# FSRs.net
KiCad netlist of a schematic drawn in Altium Designer
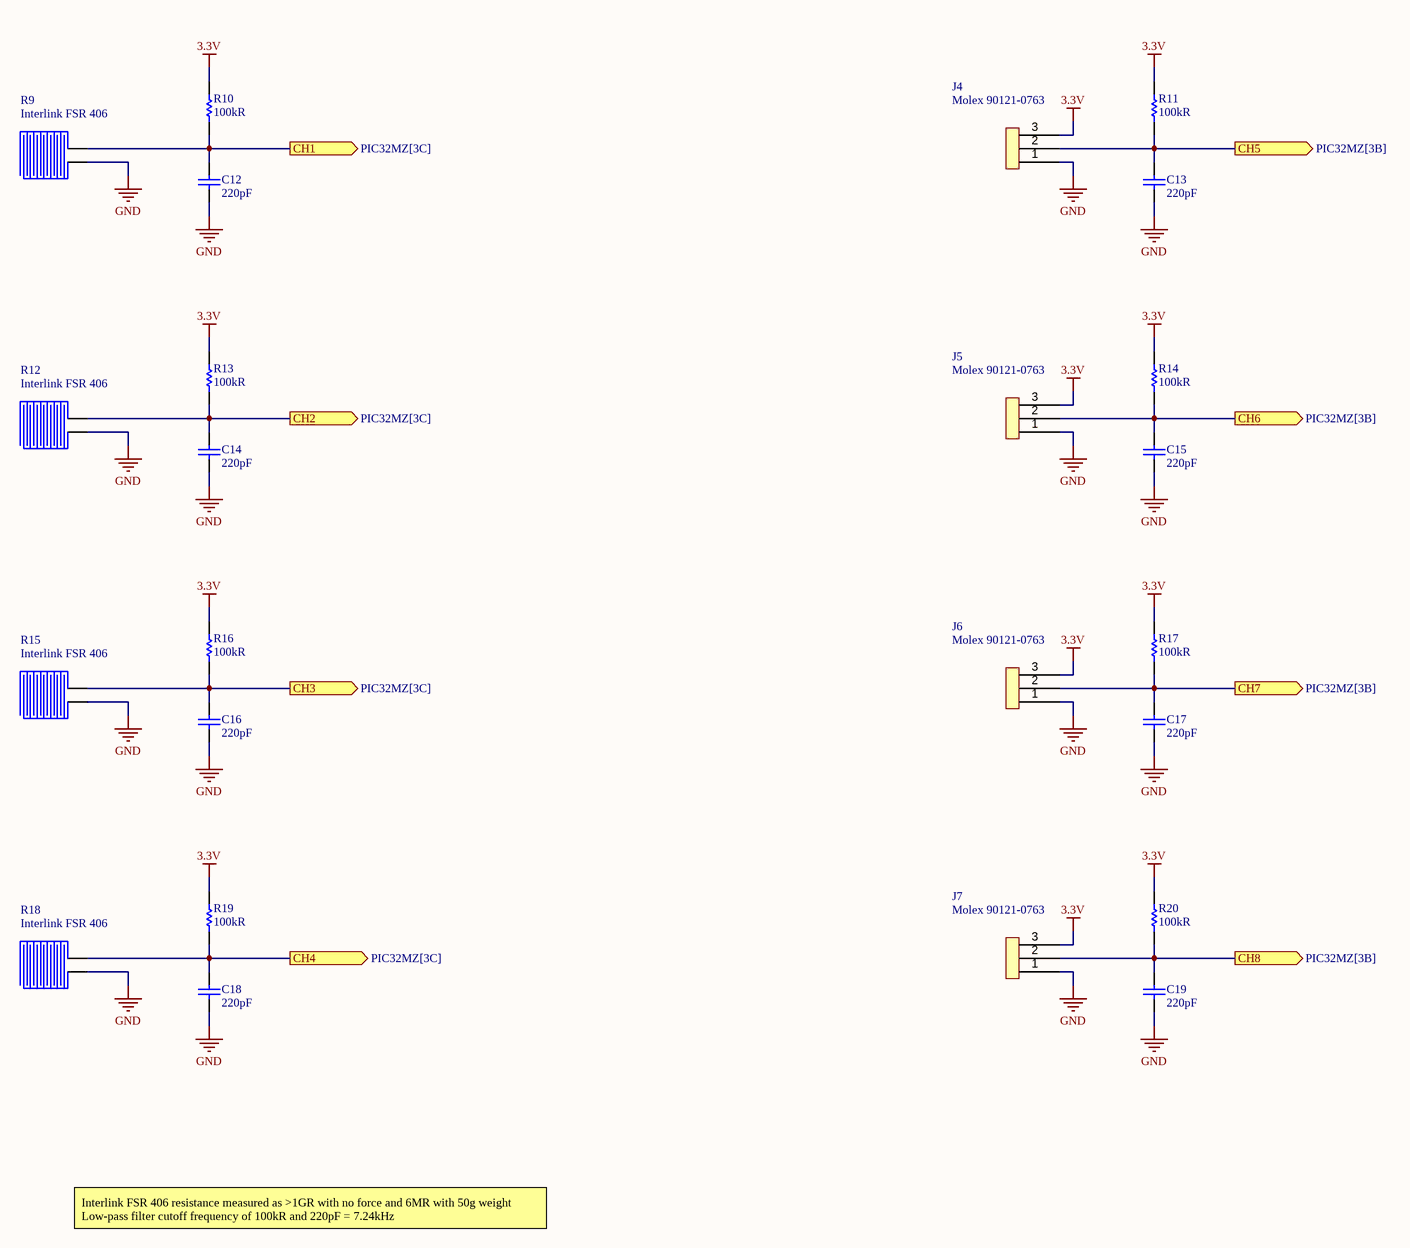
[diagram p0: FSRs.SchDoc]

(export (version "E")
  (design (tool "Eeschema 10.0.6"))
  (components
    (comp (ref "C12")
      (value "220pF")
      (footprint "Capacitor 0402")
      (libsource (lib "x-io") (part "Capacitor"))
    )
    (comp (ref "C13")
      (value "220pF")
      (footprint "Capacitor 0402")
      (libsource (lib "x-io") (part "Capacitor"))
    )
    (comp (ref "C14")
      (value "220pF")
      (footprint "Capacitor 0402")
      (libsource (lib "x-io") (part "Capacitor"))
    )
    (comp (ref "C15")
      (value "220pF")
      (footprint "Capacitor 0402")
      (libsource (lib "x-io") (part "Capacitor"))
    )
    (comp (ref "C16")
      (value "220pF")
      (footprint "Capacitor 0402")
      (libsource (lib "x-io") (part "Capacitor"))
    )
    (comp (ref "C17")
      (value "220pF")
      (footprint "Capacitor 0402")
      (libsource (lib "x-io") (part "Capacitor"))
    )
    (comp (ref "C18")
      (value "220pF")
      (footprint "Capacitor 0402")
      (libsource (lib "x-io") (part "Capacitor"))
    )
    (comp (ref "C19")
      (value "220pF")
      (footprint "Capacitor 0402")
      (libsource (lib "x-io") (part "Capacitor"))
    )
    (comp (ref "J4")
      (value "Molex 90121-0763")
      (footprint "Molex 90121-0763")
      (libsource (lib "x-io") (part "Molex 90121-0763"))
    )
    (comp (ref "J5")
      (value "Molex 90121-0763")
      (footprint "Molex 90121-0763")
      (libsource (lib "x-io") (part "Molex 90121-0763"))
    )
    (comp (ref "J6")
      (value "Molex 90121-0763")
      (footprint "Molex 90121-0763")
      (libsource (lib "x-io") (part "Molex 90121-0763"))
    )
    (comp (ref "J7")
      (value "Molex 90121-0763")
      (footprint "Molex 90121-0763")
      (libsource (lib "x-io") (part "Molex 90121-0763"))
    )
    (comp (ref "R9")
      (value "Interlink FSR 406")
      (footprint "Interlink FSR 406")
      (libsource (lib "x-io") (part "Interlink FSR 406"))
    )
    (comp (ref "R10") (value "100kR") (footprint "Resistor 0402") (libsource (lib "x-io") (part "Resistor")))
    (comp (ref "R11") (value "100kR") (footprint "Resistor 0402") (libsource (lib "x-io") (part "Resistor")))
    (comp (ref "R12")
      (value "Interlink FSR 406")
      (footprint "Interlink FSR 406")
      (libsource (lib "x-io") (part "Interlink FSR 406"))
    )
    (comp (ref "R13") (value "100kR") (footprint "Resistor 0402") (libsource (lib "x-io") (part "Resistor")))
    (comp (ref "R14") (value "100kR") (footprint "Resistor 0402") (libsource (lib "x-io") (part "Resistor")))
    (comp (ref "R15")
      (value "Interlink FSR 406")
      (footprint "Interlink FSR 406")
      (libsource (lib "x-io") (part "Interlink FSR 406"))
    )
    (comp (ref "R16") (value "100kR") (footprint "Resistor 0402") (libsource (lib "x-io") (part "Resistor")))
    (comp (ref "R17") (value "100kR") (footprint "Resistor 0402") (libsource (lib "x-io") (part "Resistor")))
    (comp (ref "R18")
      (value "Interlink FSR 406")
      (footprint "Interlink FSR 406")
      (libsource (lib "x-io") (part "Interlink FSR 406"))
    )
    (comp (ref "R19") (value "100kR") (footprint "Resistor 0402") (libsource (lib "x-io") (part "Resistor")))
    (comp (ref "R20") (value "100kR") (footprint "Resistor 0402") (libsource (lib "x-io") (part "Resistor")))
  )
  (nets
    (net (code "1") (name "/CH1") (class "Default")
      (node (ref "C12") (pin "2") (pinfunction "2_2") (pintype "passive"))
      (node (ref "R10") (pin "1") (pinfunction "1_1") (pintype "passive"))
      (node (ref "R9") (pin "1") (pinfunction "1_1") (pintype "passive"))
    )
    (net (code "2") (name "/CH2") (class "Default")
      (node (ref "C14") (pin "2") (pinfunction "2_2") (pintype "passive"))
      (node (ref "R12") (pin "1") (pinfunction "1_1") (pintype "passive"))
      (node (ref "R13") (pin "1") (pinfunction "1_1") (pintype "passive"))
    )
    (net (code "3") (name "/CH3") (class "Default")
      (node (ref "C16") (pin "2") (pinfunction "2_2") (pintype "passive"))
      (node (ref "R15") (pin "1") (pinfunction "1_1") (pintype "passive"))
      (node (ref "R16") (pin "1") (pinfunction "1_1") (pintype "passive"))
    )
    (net (code "4") (name "/CH4") (class "Default")
      (node (ref "C18") (pin "2") (pinfunction "2_2") (pintype "passive"))
      (node (ref "R18") (pin "1") (pinfunction "1_1") (pintype "passive"))
      (node (ref "R19") (pin "1") (pinfunction "1_1") (pintype "passive"))
    )
    (net (code "5") (name "/CH5") (class "Default")
      (node (ref "C13") (pin "2") (pinfunction "2_2") (pintype "passive"))
      (node (ref "J4") (pin "2") (pinfunction "2_2") (pintype "passive"))
      (node (ref "R11") (pin "1") (pinfunction "1_1") (pintype "passive"))
    )
    (net (code "6") (name "/CH6") (class "Default")
      (node (ref "C15") (pin "2") (pinfunction "2_2") (pintype "passive"))
      (node (ref "J5") (pin "2") (pinfunction "2_2") (pintype "passive"))
      (node (ref "R14") (pin "1") (pinfunction "1_1") (pintype "passive"))
    )
    (net (code "7") (name "/CH7") (class "Default")
      (node (ref "C17") (pin "2") (pinfunction "2_2") (pintype "passive"))
      (node (ref "J6") (pin "2") (pinfunction "2_2") (pintype "passive"))
      (node (ref "R17") (pin "1") (pinfunction "1_1") (pintype "passive"))
    )
    (net (code "8") (name "/CH8") (class "Default")
      (node (ref "C19") (pin "2") (pinfunction "2_2") (pintype "passive"))
      (node (ref "J7") (pin "2") (pinfunction "2_2") (pintype "passive"))
      (node (ref "R20") (pin "1") (pinfunction "1_1") (pintype "passive"))
    )
    (net (code "9") (name "3.3V") (class "Default")
      (node (ref "J4") (pin "3") (pinfunction "3_3") (pintype "passive"))
      (node (ref "J5") (pin "3") (pinfunction "3_3") (pintype "passive"))
      (node (ref "J6") (pin "3") (pinfunction "3_3") (pintype "passive"))
      (node (ref "J7") (pin "3") (pinfunction "3_3") (pintype "passive"))
      (node (ref "R10") (pin "2") (pinfunction "2_2") (pintype "passive"))
      (node (ref "R11") (pin "2") (pinfunction "2_2") (pintype "passive"))
      (node (ref "R13") (pin "2") (pinfunction "2_2") (pintype "passive"))
      (node (ref "R14") (pin "2") (pinfunction "2_2") (pintype "passive"))
      (node (ref "R16") (pin "2") (pinfunction "2_2") (pintype "passive"))
      (node (ref "R17") (pin "2") (pinfunction "2_2") (pintype "passive"))
      (node (ref "R19") (pin "2") (pinfunction "2_2") (pintype "passive"))
      (node (ref "R20") (pin "2") (pinfunction "2_2") (pintype "passive"))
    )
    (net (code "10") (name "GND") (class "Default")
      (node (ref "C12") (pin "1") (pinfunction "1_1") (pintype "passive"))
      (node (ref "C13") (pin "1") (pinfunction "1_1") (pintype "passive"))
      (node (ref "C14") (pin "1") (pinfunction "1_1") (pintype "passive"))
      (node (ref "C15") (pin "1") (pinfunction "1_1") (pintype "passive"))
      (node (ref "C16") (pin "1") (pinfunction "1_1") (pintype "passive"))
      (node (ref "C17") (pin "1") (pinfunction "1_1") (pintype "passive"))
      (node (ref "C18") (pin "1") (pinfunction "1_1") (pintype "passive"))
      (node (ref "C19") (pin "1") (pinfunction "1_1") (pintype "passive"))
      (node (ref "J4") (pin "1") (pinfunction "1_1") (pintype "passive"))
      (node (ref "J5") (pin "1") (pinfunction "1_1") (pintype "passive"))
      (node (ref "J6") (pin "1") (pinfunction "1_1") (pintype "passive"))
      (node (ref "J7") (pin "1") (pinfunction "1_1") (pintype "passive"))
      (node (ref "R12") (pin "2") (pinfunction "2_2") (pintype "passive"))
      (node (ref "R15") (pin "2") (pinfunction "2_2") (pintype "passive"))
      (node (ref "R18") (pin "2") (pinfunction "2_2") (pintype "passive"))
      (node (ref "R9") (pin "2") (pinfunction "2_2") (pintype "passive"))
    )
  )
)
